# Sheet1.net
KiCad netlist of a schematic drawn in Altium Designer
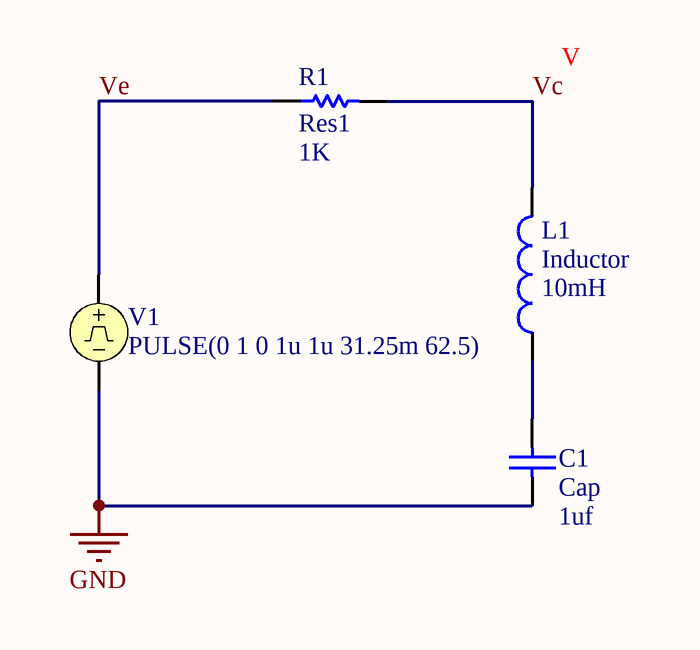
[diagram p0: Sheet1.SchDoc]

(export (version "E")
  (design (tool "Eeschema 10.0.6"))
  (components
    (comp (ref "C1")
      (value "Cap")
      (footprint "RAD-0.3")
      (description "Capacitor")
      (fields (field (name "ALTIUM_VALUE") "1uf") (field (name "PUBLISHER") "Altium Limited"))
      (libsource (lib "Miscellaneous Devices") (part "Cap"))
    )
    (comp (ref "L1")
      (value "Inductor")
      (footprint "0402-A")
      (fields (field (name "ALTIUM_VALUE") "10mH") (field (name "PUBLISHER") "Altium Limited"))
      (libsource (lib "Miscellaneous Devices") (part "Inductor"))
    )
    (comp (ref "R1")
      (value "Res1")
      (footprint "AXIAL-0.3")
      (description "Resistor")
      (fields (field (name "ALTIUM_VALUE") "1K") (field (name "PUBLISHER") "Altium Limited"))
      (libsource (lib "Miscellaneous Devices") (part "Res1"))
    )
    (comp (ref "V1")
      (value "PULSE(0 1 0 1u 1u 31.25m 62.5)")
      (description "Pulse Voltage Source")
      (fields (field (name "PUBLISHER") "Altium Limited"))
      (libsource (lib "Simulation Sources") (part "VPULSE"))
    )
  )
  (nets
    (net (code "1") (name "/Vc") (class "Default")
      (node (ref "L1") (pin "2") (pinfunction "2_2") (pintype "passive"))
      (node (ref "R1") (pin "2") (pinfunction "2_2") (pintype "passive"))
    )
    (net (code "2") (name "/Ve") (class "Default")
      (node (ref "R1") (pin "1") (pinfunction "1_1") (pintype "passive"))
      (node (ref "V1") (pin "1") (pinfunction "1_1") (pintype "passive"))
    )
    (net (code "3") (name "GND") (class "Default")
      (node (ref "C1") (pin "2") (pinfunction "2_2") (pintype "passive"))
      (node (ref "V1") (pin "2") (pinfunction "2_2") (pintype "passive"))
    )
    (net (code "4") (name "Net-(C1-Pad1)") (class "Default")
      (node (ref "C1") (pin "1") (pinfunction "1_1") (pintype "passive"))
      (node (ref "L1") (pin "1") (pinfunction "1_1") (pintype "passive"))
    )
  )
)
